# ArrayDiodeBoard.net
KiCad netlist of a schematic drawn in Altium Designer
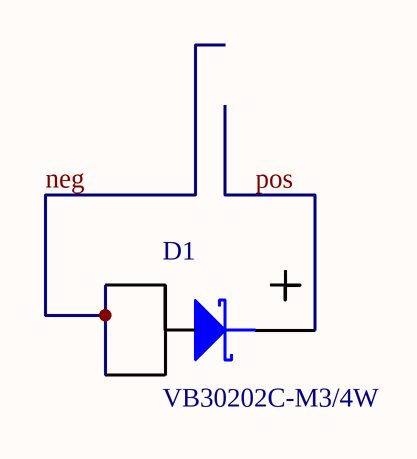
[diagram p0: ArrayDiodeBoard.SchDoc]

(export (version "E")
  (design (tool "Eeschema 10.0.6"))
  (components
    (comp (ref "D1")
      (value "VB30202C-M3/4W")
      (footprint "D2PAK")
      (libsource (lib "Common") (part "Active Array Diode SM74611KTTR"))
    )
  )
  (nets
    (net (code "1") (name "/neg") (class "Default")
      (node (ref "D1") (pin "1") (pinfunction "A1_1") (pintype "passive"))
      (node (ref "D1") (pin "3") (pinfunction "A2_3") (pintype "passive"))
    )
    (net (code "2") (name "/pos") (class "Default")
      (node (ref "D1") (pin "2") (pinfunction "K_2") (pintype "passive"))
    )
  )
)
